# SCH_ATC-PCB-SMD-V1_5_2024-12-07.net
KiCad netlist of a schematic drawn in EasyEDA
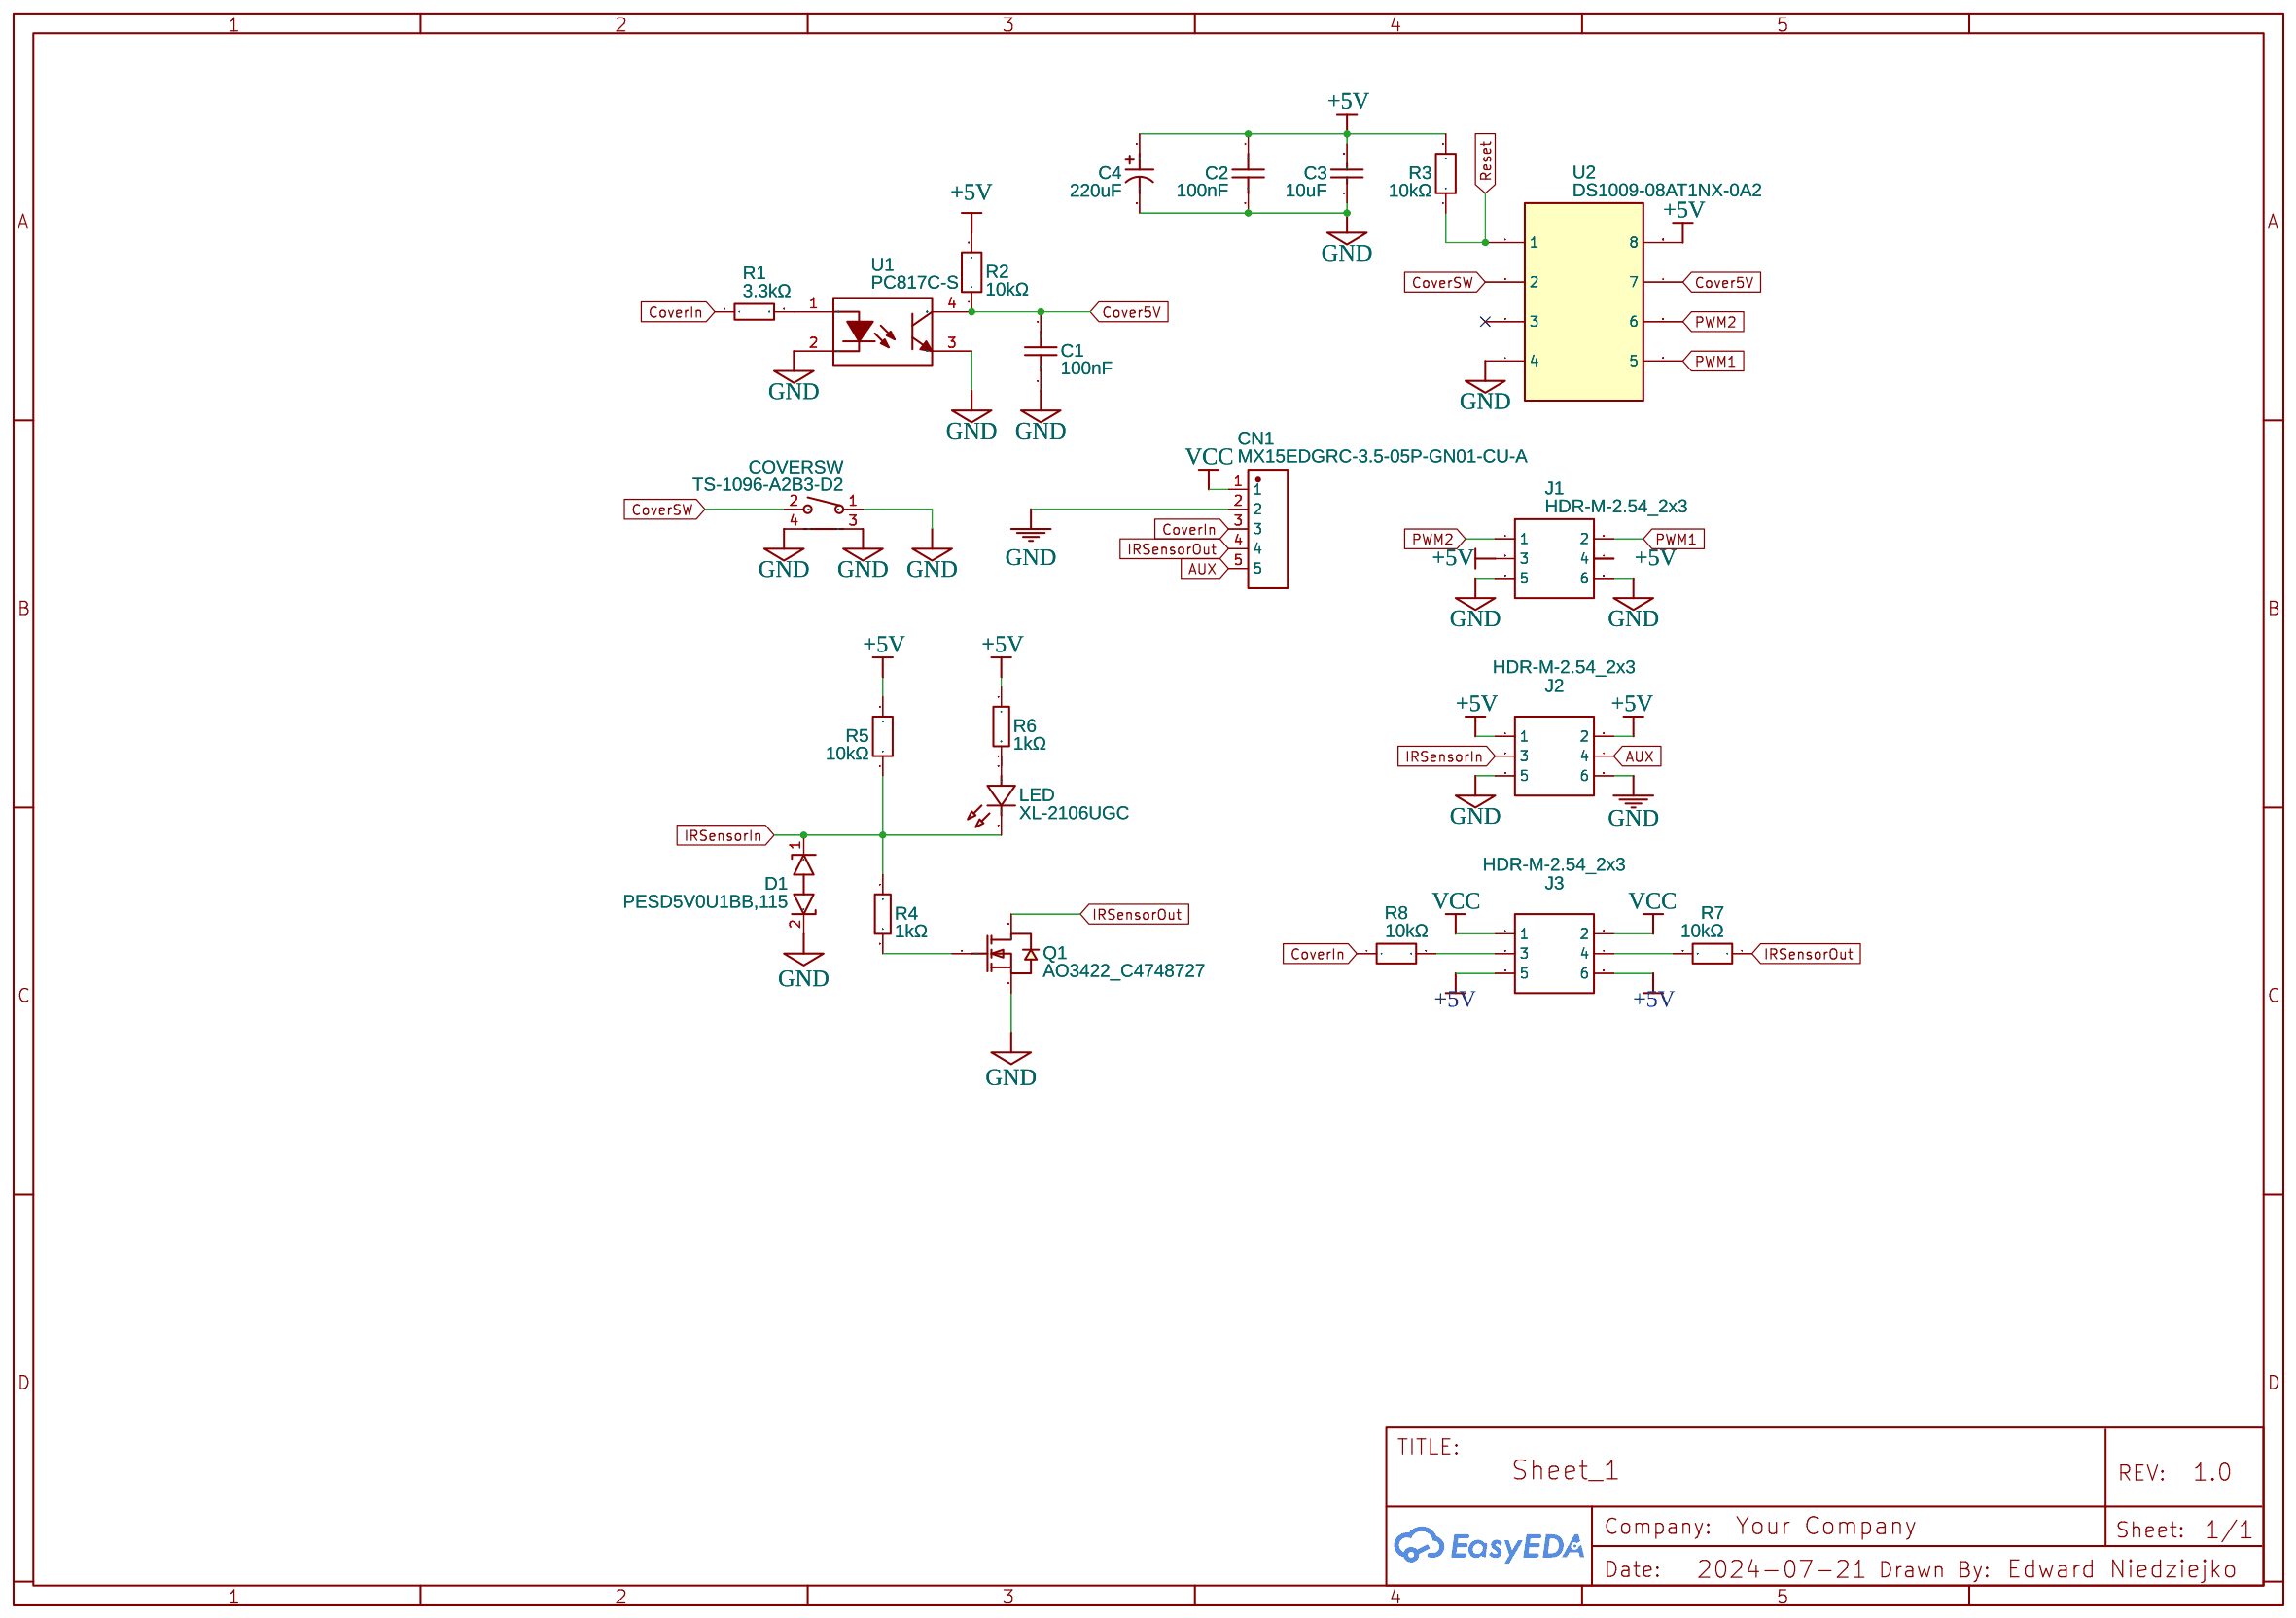
[diagram p0: schematic sheet]

(export (version "E")
  (design (tool "Eeschema 10.0.6"))
  (components
    (comp (ref "C1")
      (value "100nF")
      (fields
        (field (name "Manufacturer Part") "CC0805JRX7R7BB104")
        (field (name "Manufacturer") "YAGEO(国巨)")
      )
      (libsource (lib "") (part "CC0805JRX7R7BB104"))
    )
    (comp (ref "C2")
      (value "100nF")
      (fields
        (field (name "Manufacturer Part") "CC0805JRX7R7BB104")
        (field (name "Manufacturer") "YAGEO(国巨)")
      )
      (libsource (lib "") (part "CC0805JRX7R7BB104_1"))
    )
    (comp (ref "C3")
      (value "10uF")
      (fields
        (field (name "Manufacturer Part") "GRM21BB31C106KE15L")
        (field (name "Manufacturer") "muRata(村田)")
      )
      (libsource (lib "") (part "GRM21BB31C106KE15L"))
    )
    (comp (ref "C4")
      (value "220uF")
      (fields
        (field (name "Manufacturer Part") "CA45-B-6.3V-220UF-M")
        (field (name "Manufacturer") "CEC(振华新云)")
      )
      (libsource (lib "") (part "CA45-B-6.3V-220UF-M"))
    )
    (comp (ref "CN1")
      (value "MX15EDGRC-3.5-05P-GN01-CU-A")
      (fields
        (field (name "Manufacturer Part") "MX15EDGRC-3.5-05P-GN01-Cu-A")
        (field (name "Manufacturer") "MAX(迈旭)")
      )
      (libsource (lib "") (part "MX15EDGRC-3.5-05P-GN01-CU-A"))
    )
    (comp (ref "COVERSW")
      (value "TS-1096-A2B3-D2")
      (fields (field (name "Manufacturer") "Yuandi(元迪)"))
      (libsource (lib "") (part "TS-1096-A2B3-D2"))
    )
    (comp (ref "D1")
      (value "PESD5V0U1BB,115")
      (fields (field (name "Manufacturer") "Nexperia(安世)"))
      (libsource (lib "") (part "PESD5V0U1BB,115"))
    )
    (comp (ref "J1") (value "HDR-M-2.54_2x3") (libsource (lib "") (part "HDR-M-2.54_2x3")))
    (comp (ref "J2") (value "HDR-M-2.54_2x3") (libsource (lib "") (part "HDR-M-2.54_2x3")))
    (comp (ref "J3") (value "HDR-M-2.54_2x3") (libsource (lib "") (part "HDR-M-2.54_2x3")))
    (comp (ref "LED")
      (value "XL-2106UGC")
      (fields (field (name "Manufacturer") "XINGLIGHT(成兴光)"))
      (libsource (lib "") (part "XL-2106UGC"))
    )
    (comp (ref "Q1")
      (value "AO3422_C4748727")
      (fields
        (field (name "Manufacturer Part") "AO3422-HXY")
        (field (name "Manufacturer") "HXY MOSFET(华轩阳电子)")
      )
      (libsource (lib "") (part "AO3422_C4748727"))
    )
    (comp (ref "R1")
      (value "3.3kΩ")
      (fields (field (name "Manufacturer Part") "RK73H2ATTD3301F") (field (name "Manufacturer") "KOA"))
      (libsource (lib "") (part "RK73H2ATTD3301F"))
    )
    (comp (ref "R2")
      (value "10kΩ")
      (fields (field (name "Manufacturer Part") "SCR0805F10K") (field (name "Manufacturer") "VO(翔胜)"))
      (libsource (lib "") (part "SCR0805F10K"))
    )
    (comp (ref "R3")
      (value "10kΩ")
      (fields (field (name "Manufacturer Part") "SCR0805F10K") (field (name "Manufacturer") "VO(翔胜)"))
      (libsource (lib "") (part "SCR0805F10K"))
    )
    (comp (ref "R4")
      (value "1kΩ")
      (fields (field (name "Manufacturer Part") "CR0805-FX-1001ELF") (field (name "Manufacturer") "BOURNS"))
      (libsource (lib "") (part "CR0805-FX-1001ELF"))
    )
    (comp (ref "R5")
      (value "10kΩ")
      (fields (field (name "Manufacturer Part") "SCR0805F10K") (field (name "Manufacturer") "VO(翔胜)"))
      (libsource (lib "") (part "SCR0805F10K"))
    )
    (comp (ref "R6")
      (value "1kΩ")
      (fields (field (name "Manufacturer Part") "CR0805-FX-1001ELF") (field (name "Manufacturer") "BOURNS"))
      (libsource (lib "") (part "CR0805-FX-1001ELF"))
    )
    (comp (ref "R7")
      (value "10kΩ")
      (fields (field (name "Manufacturer Part") "SCR0805F10K") (field (name "Manufacturer") "VO(翔胜)"))
      (libsource (lib "") (part "SCR0805F10K_1"))
    )
    (comp (ref "R8")
      (value "10kΩ")
      (fields (field (name "Manufacturer Part") "SCR0805F10K") (field (name "Manufacturer") "VO(翔胜)"))
      (libsource (lib "") (part "SCR0805F10K_2"))
    )
    (comp (ref "U1")
      (value "PC817C-S")
      (fields (field (name "Manufacturer") "UMW(友台半导体)"))
      (libsource (lib "") (part "PC817C-S"))
    )
    (comp (ref "U2")
      (value "DS1009-08AT1NX-0A2")
      (fields (field (name "Manufacturer") "CONNFLY"))
      (libsource (lib "") (part "DS1009-08AT1NX-0A2"))
    )
  )
  (nets
    (net (code "1") (name "+5V") (class "Default")
      (node (ref "C2") (pin "1") (pinfunction "1_1") (pintype "unspecified"))
      (node (ref "C3") (pin "2") (pinfunction "2_2") (pintype "input"))
      (node (ref "C4") (pin "1") (pinfunction "1_1") (pintype "input"))
      (node (ref "J1") (pin "3") (pinfunction "3_3") (pintype "input"))
      (node (ref "J1") (pin "4") (pinfunction "4_4") (pintype "input"))
      (node (ref "J2") (pin "1") (pinfunction "1_1") (pintype "input"))
      (node (ref "J2") (pin "2") (pinfunction "2_2") (pintype "input"))
      (node (ref "J3") (pin "5") (pinfunction "5_5") (pintype "input"))
      (node (ref "J3") (pin "6") (pinfunction "6_6") (pintype "input"))
      (node (ref "R2") (pin "2") (pinfunction "2_2") (pintype "unspecified"))
      (node (ref "R3") (pin "2") (pinfunction "2_2") (pintype "unspecified"))
      (node (ref "R5") (pin "2") (pinfunction "2_2") (pintype "unspecified"))
      (node (ref "R6") (pin "1") (pinfunction "1_1") (pintype "unspecified"))
      (node (ref "U2") (pin "8") (pinfunction "8_8") (pintype "input"))
    )
    (net (code "2") (name "AUX") (class "Default")
      (node (ref "CN1") (pin "5") (pinfunction "5_5") (pintype "unspecified"))
      (node (ref "J2") (pin "4") (pinfunction "4_4") (pintype "input"))
    )
    (net (code "3") (name "Cover5V") (class "Default")
      (node (ref "C1") (pin "1") (pinfunction "1_1") (pintype "unspecified"))
      (node (ref "R2") (pin "1") (pinfunction "1_1") (pintype "unspecified"))
      (node (ref "U1") (pin "4") (pinfunction "COL_4") (pintype "unspecified"))
      (node (ref "U2") (pin "7") (pinfunction "7_7") (pintype "input"))
    )
    (net (code "4") (name "CoverIn") (class "Default")
      (node (ref "CN1") (pin "3") (pinfunction "3_3") (pintype "unspecified"))
      (node (ref "R1") (pin "1") (pinfunction "1_1") (pintype "unspecified"))
      (node (ref "R8") (pin "1") (pinfunction "1_1") (pintype "unspecified"))
    )
    (net (code "5") (name "CoverSW") (class "Default")
      (node (ref "COVERSW") (pin "2") (pinfunction "2_2") (pintype "unspecified"))
      (node (ref "U2") (pin "2") (pinfunction "2_2") (pintype "input"))
    )
    (net (code "6") (name "GND") (class "Default")
      (node (ref "C1") (pin "2") (pinfunction "2_2") (pintype "unspecified"))
      (node (ref "C2") (pin "2") (pinfunction "2_2") (pintype "unspecified"))
      (node (ref "C3") (pin "1") (pinfunction "1_1") (pintype "input"))
      (node (ref "C4") (pin "2") (pinfunction "2_2") (pintype "input"))
      (node (ref "CN1") (pin "2") (pinfunction "2_2") (pintype "unspecified"))
      (node (ref "COVERSW") (pin "1") (pinfunction "1_1") (pintype "unspecified"))
      (node (ref "COVERSW") (pin "3") (pinfunction "EP_3") (pintype "unspecified"))
      (node (ref "COVERSW") (pin "4") (pinfunction "EP_4") (pintype "unspecified"))
      (node (ref "D1") (pin "2") (pinfunction "2_2") (pintype "unspecified"))
      (node (ref "J1") (pin "5") (pinfunction "5_5") (pintype "input"))
      (node (ref "J1") (pin "6") (pinfunction "6_6") (pintype "input"))
      (node (ref "J2") (pin "5") (pinfunction "5_5") (pintype "input"))
      (node (ref "J2") (pin "6") (pinfunction "6_6") (pintype "input"))
      (node (ref "Q1") (pin "2") (pinfunction "S_2") (pintype "unspecified"))
      (node (ref "U1") (pin "2") (pinfunction "CAT_2") (pintype "unspecified"))
      (node (ref "U1") (pin "3") (pinfunction "EM_3") (pintype "unspecified"))
      (node (ref "U2") (pin "4") (pinfunction "4_4") (pintype "input"))
    )
    (net (code "7") (name "IRSensorIn") (class "Default")
      (node (ref "D1") (pin "1") (pinfunction "1_1") (pintype "unspecified"))
      (node (ref "J2") (pin "3") (pinfunction "3_3") (pintype "input"))
      (node (ref "LED") (pin "1") (pinfunction "K_1") (pintype "unspecified"))
      (node (ref "R4") (pin "1") (pinfunction "1_1") (pintype "unspecified"))
      (node (ref "R5") (pin "1") (pinfunction "1_1") (pintype "unspecified"))
    )
    (net (code "8") (name "IRSensorOut") (class "Default")
      (node (ref "CN1") (pin "4") (pinfunction "4_4") (pintype "unspecified"))
      (node (ref "Q1") (pin "3") (pinfunction "D_3") (pintype "unspecified"))
      (node (ref "R7") (pin "1") (pinfunction "1_1") (pintype "unspecified"))
    )
    (net (code "9") (name "Net-(J3-Pad3)") (class "Default")
      (node (ref "J3") (pin "3") (pinfunction "3_3") (pintype "input"))
      (node (ref "R8") (pin "2") (pinfunction "2_2") (pintype "unspecified"))
    )
    (net (code "10") (name "Net-(J3-Pad4)") (class "Default")
      (node (ref "J3") (pin "4") (pinfunction "4_4") (pintype "input"))
      (node (ref "R7") (pin "2") (pinfunction "2_2") (pintype "unspecified"))
    )
    (net (code "11") (name "Net-(LED-A)") (class "Default")
      (node (ref "LED") (pin "2") (pinfunction "A_2") (pintype "unspecified"))
      (node (ref "R6") (pin "2") (pinfunction "2_2") (pintype "unspecified"))
    )
    (net (code "12") (name "Net-(Q1-G)") (class "Default")
      (node (ref "Q1") (pin "1") (pinfunction "G_1") (pintype "unspecified"))
      (node (ref "R4") (pin "2") (pinfunction "2_2") (pintype "unspecified"))
    )
    (net (code "13") (name "Net-(U1-AN)") (class "Default")
      (node (ref "R1") (pin "2") (pinfunction "2_2") (pintype "unspecified"))
      (node (ref "U1") (pin "1") (pinfunction "AN_1") (pintype "unspecified"))
    )
    (net (code "14") (name "PWM1") (class "Default")
      (node (ref "J1") (pin "2") (pinfunction "2_2") (pintype "input"))
      (node (ref "U2") (pin "5") (pinfunction "5_5") (pintype "input"))
    )
    (net (code "15") (name "PWM2") (class "Default")
      (node (ref "J1") (pin "1") (pinfunction "1_1") (pintype "input"))
      (node (ref "U2") (pin "6") (pinfunction "6_6") (pintype "input"))
    )
    (net (code "16") (name "Reset") (class "Default")
      (node (ref "R3") (pin "1") (pinfunction "1_1") (pintype "unspecified"))
      (node (ref "U2") (pin "1") (pinfunction "1_1") (pintype "input"))
    )
    (net (code "17") (name "VCC") (class "Default")
      (node (ref "CN1") (pin "1") (pinfunction "1_1") (pintype "unspecified"))
      (node (ref "J3") (pin "1") (pinfunction "1_1") (pintype "input"))
      (node (ref "J3") (pin "2") (pinfunction "2_2") (pintype "input"))
    )
    (net (code "18") (name "unconnected-(U2-Pad3)") (class "Default")
      (node (ref "U2") (pin "3") (pinfunction "3_3") (pintype "input+no_connect"))
    )
  )
)
